# Auxillary.net
KiCad netlist of a schematic drawn in EAGLE
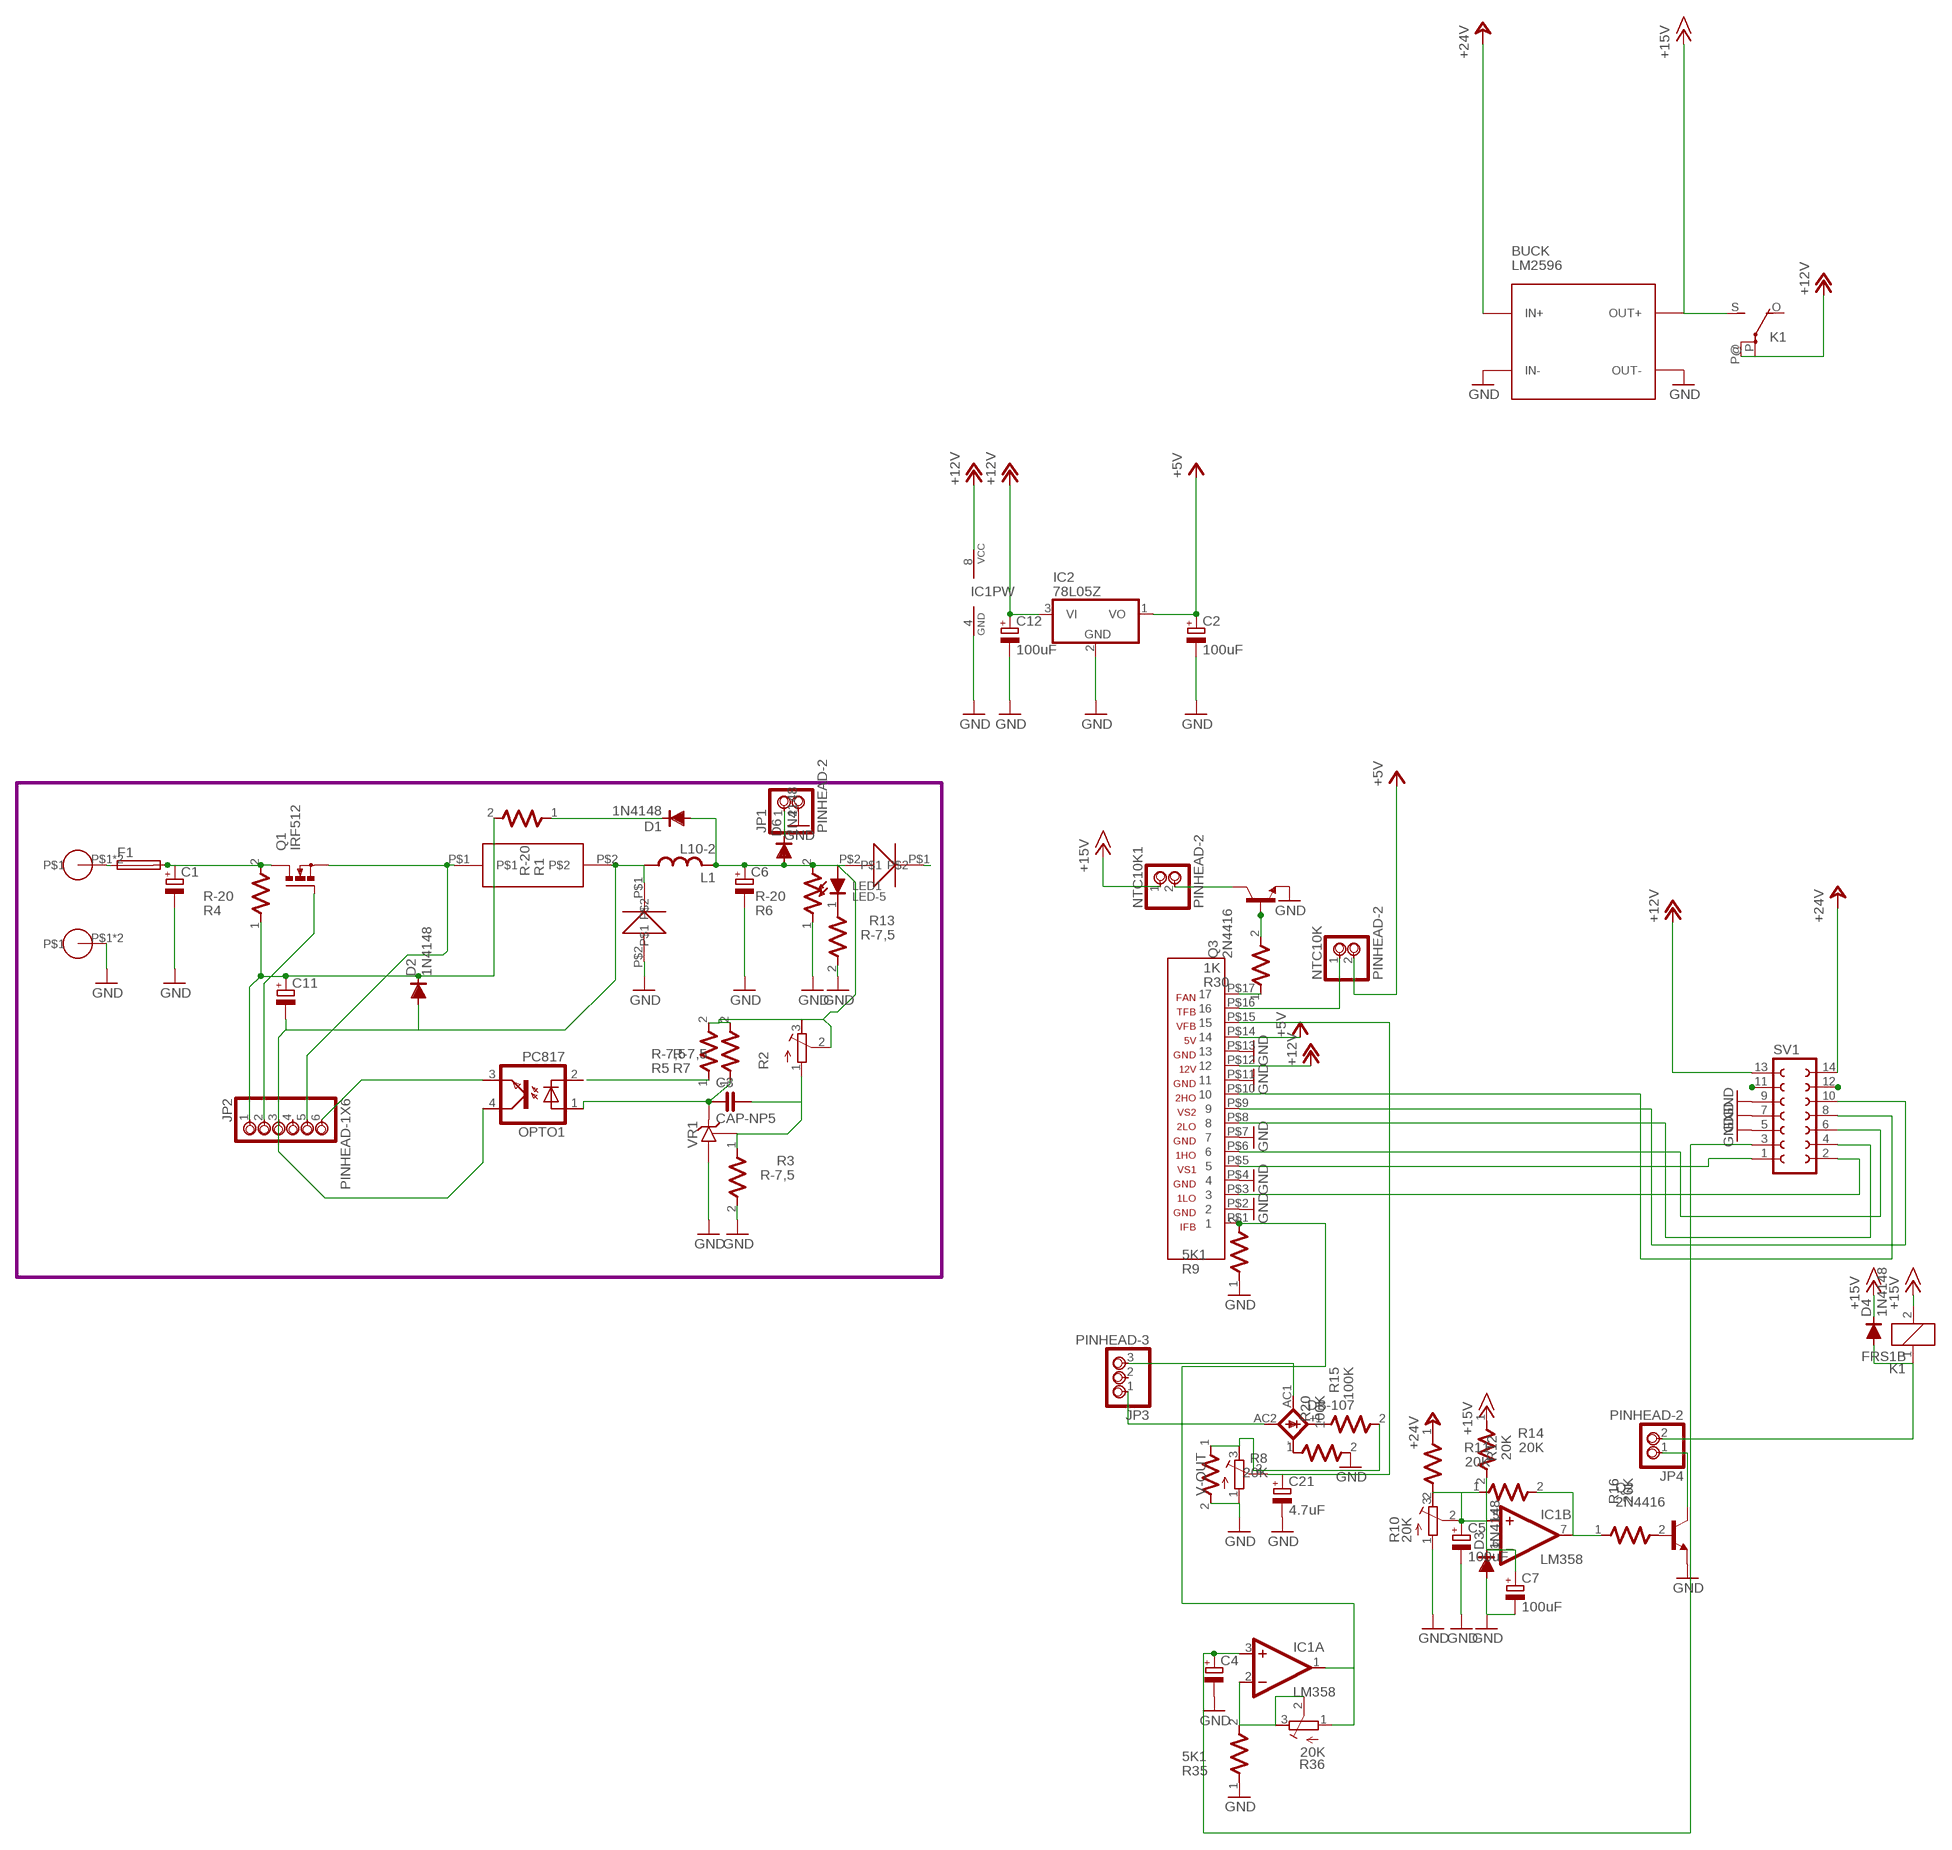
[diagram p0: schematic, sheet 1]

(export (version "E")
  (design (tool "Eeschema 10.0.6"))
  (components
    (comp (ref "BUCK")
      (value "LM2596")
      (footprint "eagle-import:DC-DC-STEP-DOWN-LM2596")
      (libsource (lib "eagle-import") (part "DC-DC-STEP-DOWN-LM2596"))
    )
    (comp (ref "C1")
      (value "CPOL-EUE7.5-18")
      (footprint "eagle-import:E7,5-18")
      (libsource (lib "eagle-import") (part "CPOL-EUE7.5-18"))
    )
    (comp (ref "C2")
      (value "100uF")
      (footprint "eagle-import:E2,5-7")
      (libsource (lib "eagle-import") (part "CPOL-EUE2.5-7"))
    )
    (comp (ref "C3")
      (value "CAP-NP5")
      (footprint "eagle-import:CAP-NP5")
      (libsource (lib "eagle-import") (part "CAP-NP5"))
    )
    (comp (ref "C4")
      (value "CPOL-EUE2.5-7")
      (footprint "eagle-import:E2,5-7")
      (libsource (lib "eagle-import") (part "CPOL-EUE2.5-7"))
    )
    (comp (ref "C5")
      (value "100uF")
      (footprint "eagle-import:E2,5-7")
      (libsource (lib "eagle-import") (part "CPOL-EUE2.5-7"))
    )
    (comp (ref "C6")
      (value "CPOL-EUE7.5-18")
      (footprint "eagle-import:E7,5-18")
      (libsource (lib "eagle-import") (part "CPOL-EUE7.5-18"))
    )
    (comp (ref "C7")
      (value "100uF")
      (footprint "eagle-import:E2,5-7")
      (libsource (lib "eagle-import") (part "CPOL-EUE2.5-7"))
    )
    (comp (ref "C11")
      (value "CPOL-EUE5-8.5")
      (footprint "eagle-import:E5-8,5")
      (libsource (lib "eagle-import") (part "CPOL-EUE5-8.5"))
    )
    (comp (ref "C12")
      (value "100uF")
      (footprint "eagle-import:E2,5-7")
      (libsource (lib "eagle-import") (part "CPOL-EUE2.5-7"))
    )
    (comp (ref "C21")
      (value "4.7uF")
      (footprint "eagle-import:E2,5-7")
      (libsource (lib "eagle-import") (part "CPOL-EUE2.5-7"))
    )
    (comp (ref "D1")
      (value "1N4148")
      (footprint "eagle-import:D-7,5")
      (libsource (lib "eagle-import") (part "1N4148"))
    )
    (comp (ref "D2")
      (value "1N4148")
      (footprint "eagle-import:D-7,5")
      (libsource (lib "eagle-import") (part "1N4148"))
    )
    (comp (ref "D3")
      (value "1N4148")
      (footprint "eagle-import:D-7,5")
      (libsource (lib "eagle-import") (part "1N4148"))
    )
    (comp (ref "D4")
      (value "1N4148")
      (footprint "eagle-import:D-7,5")
      (libsource (lib "eagle-import") (part "1N4148"))
    )
    (comp (ref "D6")
      (value "1N4148")
      (footprint "eagle-import:D-7,5")
      (libsource (lib "eagle-import") (part "1N4148"))
    )
    (comp (ref "DB-107")
      (value "CAU-1A")
      (footprint "eagle-import:CAU-1A")
      (libsource (lib "eagle-import") (part "CAU-1A"))
    )
    (comp (ref "F1")
      (value "SH22")
      (footprint "eagle-import:SH22")
      (libsource (lib "eagle-import") (part "SH22"))
    )
    (comp (ref "IC1")
      (value "LM358")
      (footprint "eagle-import:DIL-8")
      (libsource (lib "eagle-import") (part "LM358"))
    )
    (comp (ref "IC2")
      (value "78L05Z")
      (footprint "eagle-import:TO92")
      (libsource (lib "eagle-import") (part "78ZL05"))
    )
    (comp (ref "JP1")
      (value "PINHEAD-2")
      (footprint "eagle-import:PINHEAD-2")
      (libsource (lib "eagle-import") (part "chuong_PINHEAD-2"))
    )
    (comp (ref "JP2")
      (value "PINHEAD-1X6")
      (footprint "eagle-import:PINHEAD-1X6")
      (libsource (lib "eagle-import") (part "PINHEAD-1X6"))
    )
    (comp (ref "JP3")
      (value "PINHEAD-3")
      (footprint "eagle-import:PINHEAD-3")
      (libsource (lib "eagle-import") (part "PINHEAD-3"))
    )
    (comp (ref "JP4")
      (value "PINHEAD-2")
      (footprint "eagle-import:PINHEAD-2")
      (libsource (lib "eagle-import") (part "chuong_PINHEAD-2"))
    )
    (comp (ref "K1")
      (value "FRS1B")
      (footprint "eagle-import:FRS1B")
      (libsource (lib "eagle-import") (part "FRS1B"))
    )
    (comp (ref "L1")
      (value "L10-2")
      (footprint "eagle-import:L10-2")
      (libsource (lib "eagle-import") (part "L10-2"))
    )
    (comp (ref "LED1")
      (value "LED-5")
      (footprint "eagle-import:LED5")
      (libsource (lib "eagle-import") (part "LED-5"))
    )
    (comp (ref "NTC10K")
      (value "PINHEAD-2")
      (footprint "eagle-import:PINHEAD-2")
      (libsource (lib "eagle-import") (part "PINHEAD-2"))
    )
    (comp (ref "NTC10K1")
      (value "PINHEAD-2")
      (footprint "eagle-import:PINHEAD-2")
      (libsource (lib "eagle-import") (part "PINHEAD-2"))
    )
    (comp (ref "OPTO1")
      (value "PC817")
      (footprint "eagle-import:DIL-04")
      (libsource (lib "eagle-import") (part "PC817"))
    )
    (comp (ref "Q1")
      (value "IRF512")
      (footprint "eagle-import:TO220BV")
      (libsource (lib "eagle-import") (part "IRF512"))
    )
    (comp (ref "Q2")
      (value "2N4416")
      (footprint "eagle-import:TO92")
      (libsource (lib "eagle-import") (part "2N4416"))
    )
    (comp (ref "Q3")
      (value "2N4416")
      (footprint "eagle-import:TO92")
      (libsource (lib "eagle-import") (part "2N4416"))
    )
    (comp (ref "R1")
      (value "R-20")
      (footprint "eagle-import:R-20")
      (libsource (lib "eagle-import") (part "R-20"))
    )
    (comp (ref "R2")
      (value "R-TRIMM64W")
      (footprint "eagle-import:RTRIM64W")
      (libsource (lib "eagle-import") (part "R-TRIMM64W"))
    )
    (comp (ref "R3")
      (value "R-7,5")
      (footprint "eagle-import:R-7,5")
      (libsource (lib "eagle-import") (part "R-7,5"))
    )
    (comp (ref "R4")
      (value "R-20")
      (footprint "eagle-import:R-20")
      (libsource (lib "eagle-import") (part "R-20"))
    )
    (comp (ref "R5")
      (value "R-7,5")
      (footprint "eagle-import:R-7,5")
      (libsource (lib "eagle-import") (part "R-7,5"))
    )
    (comp (ref "R6")
      (value "R-20")
      (footprint "eagle-import:R-20")
      (libsource (lib "eagle-import") (part "R-20"))
    )
    (comp (ref "R7")
      (value "R-7,5")
      (footprint "eagle-import:R-7,5")
      (libsource (lib "eagle-import") (part "R-7,5"))
    )
    (comp (ref "R8")
      (value "20K")
      (footprint "eagle-import:R-7,5")
      (libsource (lib "eagle-import") (part "R-7,5"))
    )
    (comp (ref "R9")
      (value "5K1")
      (footprint "eagle-import:R-7,5")
      (libsource (lib "eagle-import") (part "R-7,5"))
    )
    (comp (ref "R10")
      (value "20K")
      (footprint "eagle-import:RTRIM64W")
      (libsource (lib "eagle-import") (part "R-TRIMM64W"))
    )
    (comp (ref "R11")
      (value "20K")
      (footprint "eagle-import:R-7,5")
      (libsource (lib "eagle-import") (part "R-7,5"))
    )
    (comp (ref "R12")
      (value "20K")
      (footprint "eagle-import:R-7,5")
      (libsource (lib "eagle-import") (part "R-7,5"))
    )
    (comp (ref "R13")
      (value "R-7,5")
      (footprint "eagle-import:R-7,5")
      (libsource (lib "eagle-import") (part "R-7,5"))
    )
    (comp (ref "R14")
      (value "20K")
      (footprint "eagle-import:R-7,5")
      (libsource (lib "eagle-import") (part "R-7,5"))
    )
    (comp (ref "R15")
      (value "100K")
      (footprint "eagle-import:R-7,5")
      (libsource (lib "eagle-import") (part "R-7,5"))
    )
    (comp (ref "R16")
      (value "20K")
      (footprint "eagle-import:R-7,5")
      (libsource (lib "eagle-import") (part "R-7,5"))
    )
    (comp (ref "R20")
      (value "100K")
      (footprint "eagle-import:R-7,5")
      (libsource (lib "eagle-import") (part "R-7,5"))
    )
    (comp (ref "R30")
      (value "1K")
      (footprint "eagle-import:R-7,5")
      (libsource (lib "eagle-import") (part "R-7,5"))
    )
    (comp (ref "R35")
      (value "5K1")
      (footprint "eagle-import:R-7,5")
      (libsource (lib "eagle-import") (part "R-7,5"))
    )
    (comp (ref "R36")
      (value "20K")
      (footprint "eagle-import:RTRIM64W")
      (libsource (lib "eagle-import") (part "R-TRIMM64W"))
    )
    (comp (ref "SV1")
      (value "FE07-2")
      (footprint "eagle-import:FE07-2")
      (libsource (lib "eagle-import") (part "FE07-2"))
    )
    (comp (ref "U$1")
      (value "DSEI6060A")
      (footprint "eagle-import:DSEI6060A")
      (libsource (lib "eagle-import") (part "DSEI6060A"))
    )
    (comp (ref "U$2")
      (value "DSEI6060A")
      (footprint "eagle-import:DSEI6060A")
      (libsource (lib "eagle-import") (part "DSEI6060A"))
    )
    (comp (ref "U$3")
      (value "PIN5MM")
      (footprint "eagle-import:PIN5MM")
      (libsource (lib "eagle-import") (part "PIN5MM"))
    )
    (comp (ref "U$4")
      (value "PIN5MM")
      (footprint "eagle-import:PIN5MM")
      (libsource (lib "eagle-import") (part "PIN5MM"))
    )
    (comp (ref "U$5")
      (value "SHUNT-0.01R")
      (footprint "eagle-import:SHUNT-0.01R")
      (libsource (lib "eagle-import") (part "SHUNT-0.01R"))
    )
    (comp (ref "U$11")
      (value "EGS002")
      (footprint "eagle-import:EGS002")
      (libsource (lib "eagle-import") (part "EGS002"))
    )
    (comp (ref "V-OUT")
      (value "R-TRIMM64W")
      (footprint "eagle-import:RTRIM64W")
      (libsource (lib "eagle-import") (part "R-TRIMM64W"))
    )
    (comp (ref "VR1")
      (value "TL431CLP")
      (footprint "eagle-import:TO92-CLP")
      (libsource (lib "eagle-import") (part "TL431CLP"))
    )
  )
  (nets
    (net (code "1") (name "+5V") (class "Default")
      (node (ref "C2") (pin "+") (pinfunction "+_+") (pintype "passive"))
      (node (ref "IC2") (pin "1") (pinfunction "VO_1") (pintype "passive"))
      (node (ref "NTC10K") (pin "2") (pinfunction "2_2") (pintype "passive"))
      (node (ref "U$11") (pin "P$14") (pinfunction "14_P$14") (pintype "bidirectional"))
    )
    (net (code "2") (name "+12V") (class "Default")
      (node (ref "C12") (pin "+") (pinfunction "+_+") (pintype "passive"))
      (node (ref "IC1") (pin "8") (pinfunction "VCC_8") (pintype "power_in"))
      (node (ref "IC2") (pin "3") (pinfunction "VI_3") (pintype "input"))
      (node (ref "K1") (pin "P") (pinfunction "P_P") (pintype "passive"))
      (node (ref "K1") (pin "P@") (pinfunction "P_P@") (pintype "passive"))
      (node (ref "SV1") (pin "13") (pinfunction "13_13") (pintype "passive"))
      (node (ref "U$11") (pin "P$12") (pinfunction "12_P$12") (pintype "bidirectional"))
    )
    (net (code "3") (name "+15V") (class "Default")
      (node (ref "BUCK") (pin "OUT+") (pinfunction "OUT+_OUT+") (pintype "bidirectional"))
      (node (ref "D4") (pin "C") (pinfunction "C_C") (pintype "passive"))
      (node (ref "K1") (pin "2") (pinfunction "2_2") (pintype "passive"))
      (node (ref "K1") (pin "S") (pinfunction "S_S") (pintype "passive"))
      (node (ref "NTC10K1") (pin "1") (pinfunction "1_1") (pintype "passive"))
      (node (ref "R14") (pin "1") (pinfunction "1_1") (pintype "passive"))
    )
    (net (code "4") (name "+24V") (class "Default")
      (node (ref "BUCK") (pin "IN+") (pinfunction "IN+_IN+") (pintype "bidirectional"))
      (node (ref "R11") (pin "1") (pinfunction "1_1") (pintype "passive"))
      (node (ref "SV1") (pin "14") (pinfunction "14_14") (pintype "passive"))
    )
    (net (code "5") (name "GND") (class "Default")
      (node (ref "BUCK") (pin "IN-") (pinfunction "IN-_IN-") (pintype "bidirectional"))
      (node (ref "BUCK") (pin "OUT-") (pinfunction "OUT-_OUT-") (pintype "bidirectional"))
      (node (ref "C1") (pin "-") (pinfunction "-_-") (pintype "passive"))
      (node (ref "C12") (pin "-") (pinfunction "-_-") (pintype "passive"))
      (node (ref "C2") (pin "-") (pinfunction "-_-") (pintype "passive"))
      (node (ref "C21") (pin "-") (pinfunction "-_-") (pintype "passive"))
      (node (ref "C4") (pin "-") (pinfunction "-_-") (pintype "passive"))
      (node (ref "C5") (pin "-") (pinfunction "-_-") (pintype "passive"))
      (node (ref "C6") (pin "-") (pinfunction "-_-") (pintype "passive"))
      (node (ref "C7") (pin "-") (pinfunction "-_-") (pintype "passive"))
      (node (ref "D3") (pin "A") (pinfunction "A_A") (pintype "passive"))
      (node (ref "IC1") (pin "4") (pinfunction "GND_4") (pintype "power_in"))
      (node (ref "IC2") (pin "2") (pinfunction "GND_2") (pintype "passive"))
      (node (ref "JP1") (pin "2") (pinfunction "2_2") (pintype "passive"))
      (node (ref "Q2") (pin "3") (pinfunction "E_3") (pintype "passive"))
      (node (ref "Q3") (pin "3") (pinfunction "E_3") (pintype "passive"))
      (node (ref "R10") (pin "1") (pinfunction "A_1") (pintype "passive"))
      (node (ref "R13") (pin "2") (pinfunction "2_2") (pintype "passive"))
      (node (ref "R20") (pin "2") (pinfunction "2_2") (pintype "passive"))
      (node (ref "R3") (pin "2") (pinfunction "2_2") (pintype "passive"))
      (node (ref "R35") (pin "1") (pinfunction "1_1") (pintype "passive"))
      (node (ref "R6") (pin "1") (pinfunction "1_1") (pintype "passive"))
      (node (ref "R8") (pin "2") (pinfunction "2_2") (pintype "passive"))
      (node (ref "R9") (pin "1") (pinfunction "1_1") (pintype "passive"))
      (node (ref "SV1") (pin "5") (pinfunction "5_5") (pintype "passive"))
      (node (ref "SV1") (pin "7") (pinfunction "7_7") (pintype "passive"))
      (node (ref "SV1") (pin "9") (pinfunction "9_9") (pintype "passive"))
      (node (ref "U$1") (pin "P$2") (pinfunction "P$2_P$2") (pintype "bidirectional"))
      (node (ref "U$11") (pin "P$11") (pinfunction "11_P$11") (pintype "bidirectional"))
      (node (ref "U$11") (pin "P$13") (pinfunction "13_P$13") (pintype "bidirectional"))
      (node (ref "U$11") (pin "P$2") (pinfunction "2_P$2") (pintype "bidirectional"))
      (node (ref "U$11") (pin "P$4") (pinfunction "4_P$4") (pintype "bidirectional"))
      (node (ref "U$11") (pin "P$7") (pinfunction "7_P$7") (pintype "bidirectional"))
      (node (ref "U$3") (pin "P$1") (pinfunction "P$1_P$1") (pintype "bidirectional"))
      (node (ref "U$3") (pin "P$2") (pinfunction "P$1_P$2") (pintype "bidirectional"))
      (node (ref "V-OUT") (pin "1") (pinfunction "A_1") (pintype "passive"))
      (node (ref "VR1") (pin "A") (pinfunction "A_A") (pintype "passive"))
    )
    (net (code "6") (name "Net-(D1-PadC)") (class "Default")
      (node (ref "D1") (pin "C") (pinfunction "C_C") (pintype "passive"))
      (node (ref "R1") (pin "1") (pinfunction "1_1") (pintype "passive"))
    )
    (net (code "7") (name "Net-(D4-PadA)") (class "Default")
      (node (ref "D4") (pin "A") (pinfunction "A_A") (pintype "passive"))
      (node (ref "JP4") (pin "2") (pinfunction "2_2") (pintype "passive"))
      (node (ref "K1") (pin "1") (pinfunction "1_1") (pintype "passive"))
    )
    (net (code "8") (name "Net-(D6-PadC)") (class "Default")
      (node (ref "D6") (pin "C") (pinfunction "C_C") (pintype "passive"))
      (node (ref "JP1") (pin "1") (pinfunction "1_1") (pintype "passive"))
    )
    (net (code "9") (name "Net-(DB-107--)") (class "Default")
      (node (ref "DB-107") (pin "AC2") (pinfunction "-_AC2") (pintype "passive"))
      (node (ref "JP3") (pin "1") (pinfunction "1_1") (pintype "passive"))
    )
    (net (code "10") (name "Net-(DB-107-AC2)") (class "Default")
      (node (ref "DB-107") (pin "-") (pinfunction "AC2_-") (pintype "passive"))
      (node (ref "R20") (pin "1") (pinfunction "1_1") (pintype "passive"))
    )
    (net (code "11") (name "Net-(DB-107-Pad+)") (class "Default")
      (node (ref "DB-107") (pin "+") (pinfunction "+_+") (pintype "passive"))
      (node (ref "R15") (pin "1") (pinfunction "1_1") (pintype "passive"))
    )
    (net (code "12") (name "Net-(DB-107-PadAC1)") (class "Default")
      (node (ref "DB-107") (pin "AC1") (pinfunction "AC1_AC1") (pintype "passive"))
      (node (ref "JP3") (pin "3") (pinfunction "3_3") (pintype "passive"))
    )
    (net (code "13") (name "Net-(F1-Pad1)") (class "Default")
      (node (ref "F1") (pin "1") (pinfunction "1_1") (pintype "passive"))
      (node (ref "U$4") (pin "P$1") (pinfunction "P$1_P$1") (pintype "bidirectional"))
      (node (ref "U$4") (pin "P$2") (pinfunction "P$1_P$2") (pintype "bidirectional"))
    )
    (net (code "14") (name "Net-(IC1A-+IN)") (class "Default")
      (node (ref "C4") (pin "+") (pinfunction "+_+") (pintype "passive"))
      (node (ref "IC1") (pin "3") (pinfunction "+IN_3") (pintype "input"))
      (node (ref "SV1") (pin "3") (pinfunction "3_3") (pintype "passive"))
    )
    (net (code "15") (name "Net-(IC1A--IN)") (class "Default")
      (node (ref "IC1") (pin "2") (pinfunction "-IN_2") (pintype "input"))
      (node (ref "R35") (pin "2") (pinfunction "2_2") (pintype "passive"))
      (node (ref "R36") (pin "2") (pinfunction "S_2") (pintype "passive"))
      (node (ref "R36") (pin "3") (pinfunction "E_3") (pintype "passive"))
    )
    (net (code "16") (name "Net-(IC1A-OUT)") (class "Default")
      (node (ref "IC1") (pin "1") (pinfunction "OUT_1") (pintype "output"))
      (node (ref "R36") (pin "1") (pinfunction "A_1") (pintype "passive"))
      (node (ref "R9") (pin "2") (pinfunction "2_2") (pintype "passive"))
      (node (ref "U$11") (pin "P$1") (pinfunction "1_P$1") (pintype "bidirectional"))
    )
    (net (code "17") (name "Net-(IC1B-+IN)") (class "Default")
      (node (ref "C5") (pin "+") (pinfunction "+_+") (pintype "passive"))
      (node (ref "IC1") (pin "5") (pinfunction "+IN_5") (pintype "input"))
      (node (ref "R10") (pin "2") (pinfunction "S_2") (pintype "passive"))
      (node (ref "R10") (pin "3") (pinfunction "E_3") (pintype "passive"))
      (node (ref "R11") (pin "2") (pinfunction "2_2") (pintype "passive"))
      (node (ref "R12") (pin "1") (pinfunction "1_1") (pintype "passive"))
    )
    (net (code "18") (name "Net-(IC1B--IN)") (class "Default")
      (node (ref "C7") (pin "+") (pinfunction "+_+") (pintype "passive"))
      (node (ref "D3") (pin "C") (pinfunction "C_C") (pintype "passive"))
      (node (ref "IC1") (pin "6") (pinfunction "-IN_6") (pintype "input"))
      (node (ref "R14") (pin "2") (pinfunction "2_2") (pintype "passive"))
    )
    (net (code "19") (name "Net-(IC1B-OUT)") (class "Default")
      (node (ref "IC1") (pin "7") (pinfunction "OUT_7") (pintype "output"))
      (node (ref "R12") (pin "2") (pinfunction "2_2") (pintype "passive"))
      (node (ref "R16") (pin "1") (pinfunction "1_1") (pintype "passive"))
    )
    (net (code "20") (name "Net-(JP2-Pad2)") (class "Default")
      (node (ref "JP2") (pin "2") (pinfunction "2_2") (pintype "passive"))
      (node (ref "Q1") (pin "G") (pinfunction "G_G") (pintype "passive"))
    )
    (net (code "21") (name "Net-(JP2-Pad5)") (class "Default")
      (node (ref "JP2") (pin "5") (pinfunction "5_5") (pintype "passive"))
      (node (ref "Q1") (pin "S") (pinfunction "S_S") (pintype "passive"))
      (node (ref "U$5") (pin "P$1") (pinfunction "P$1_P$1") (pintype "bidirectional"))
    )
    (net (code "22") (name "Net-(LED1-PadK)") (class "Default")
      (node (ref "LED1") (pin "K") (pinfunction "K_K") (pintype "passive"))
      (node (ref "R13") (pin "1") (pinfunction "1_1") (pintype "passive"))
    )
    (net (code "23") (name "Net-(OPTO1-A)") (class "Default")
      (node (ref "C3") (pin "1") (pinfunction "1_1") (pintype "passive"))
      (node (ref "OPTO1") (pin "1") (pinfunction "A_1") (pintype "passive"))
      (node (ref "R7") (pin "1") (pinfunction "1_1") (pintype "passive"))
      (node (ref "VR1") (pin "C") (pinfunction "C_C") (pintype "passive"))
    )
    (net (code "24") (name "Net-(OPTO1-COL)") (class "Default")
      (node (ref "C11") (pin "-") (pinfunction "-_-") (pintype "passive"))
      (node (ref "D2") (pin "A") (pinfunction "A_A") (pintype "passive"))
      (node (ref "JP2") (pin "3") (pinfunction "3_3") (pintype "passive"))
      (node (ref "L1") (pin "P$1") (pinfunction "1_P$1") (pintype "passive"))
      (node (ref "L1") (pin "P$2") (pinfunction "1_P$2") (pintype "passive"))
      (node (ref "OPTO1") (pin "4") (pinfunction "COL_4") (pintype "passive"))
      (node (ref "U$1") (pin "P$1") (pinfunction "P$1_P$1") (pintype "bidirectional"))
      (node (ref "U$5") (pin "P$2") (pinfunction "P$2_P$2") (pintype "bidirectional"))
    )
    (net (code "25") (name "Net-(OPTO1-EMI)") (class "Default")
      (node (ref "JP2") (pin "6") (pinfunction "6_6") (pintype "passive"))
      (node (ref "OPTO1") (pin "3") (pinfunction "EMI_3") (pintype "passive"))
    )
    (net (code "26") (name "Net-(Q2-B)") (class "Default")
      (node (ref "Q2") (pin "2") (pinfunction "B_2") (pintype "passive"))
      (node (ref "R16") (pin "2") (pinfunction "2_2") (pintype "passive"))
    )
    (net (code "27") (name "Net-(Q2-C)") (class "Default")
      (node (ref "JP4") (pin "1") (pinfunction "1_1") (pintype "passive"))
      (node (ref "Q2") (pin "1") (pinfunction "C_1") (pintype "passive"))
    )
    (net (code "28") (name "Net-(Q3-B)") (class "Default")
      (node (ref "Q3") (pin "2") (pinfunction "B_2") (pintype "passive"))
      (node (ref "R30") (pin "2") (pinfunction "2_2") (pintype "passive"))
    )
    (net (code "29") (name "Net-(Q3-C)") (class "Default")
      (node (ref "NTC10K1") (pin "2") (pinfunction "2_2") (pintype "passive"))
      (node (ref "Q3") (pin "1") (pinfunction "C_1") (pintype "passive"))
    )
    (net (code "30") (name "Net-(R1-3)") (class "Default")
      (node (ref "C11") (pin "+") (pinfunction "+_+") (pintype "passive"))
      (node (ref "D2") (pin "C") (pinfunction "C_C") (pintype "passive"))
      (node (ref "JP2") (pin "1") (pinfunction "1_1") (pintype "passive"))
      (node (ref "R1") (pin "2") (pinfunction "3_2") (pintype "passive"))
      (node (ref "R4") (pin "1") (pinfunction "1_1") (pintype "passive"))
    )
    (net (code "31") (name "Net-(R2-A)") (class "Default")
      (node (ref "C3") (pin "2") (pinfunction "2_2") (pintype "passive"))
      (node (ref "R2") (pin "1") (pinfunction "A_1") (pintype "passive"))
      (node (ref "R3") (pin "1") (pinfunction "1_1") (pintype "passive"))
      (node (ref "VR1") (pin "R") (pinfunction "R_R") (pintype "passive"))
    )
    (net (code "32") (name "Net-(R2-E)") (class "Default")
      (node (ref "C6") (pin "+") (pinfunction "+_+") (pintype "passive"))
      (node (ref "D1") (pin "A") (pinfunction "A_A") (pintype "passive"))
      (node (ref "D6") (pin "A") (pinfunction "A_A") (pintype "passive"))
      (node (ref "L1") (pin "P$3") (pinfunction "2_P$3") (pintype "passive"))
      (node (ref "L1") (pin "P$4") (pinfunction "2_P$4") (pintype "passive"))
      (node (ref "LED1") (pin "A") (pinfunction "A_A") (pintype "passive"))
      (node (ref "R2") (pin "2") (pinfunction "S_2") (pintype "passive"))
      (node (ref "R2") (pin "3") (pinfunction "E_3") (pintype "passive"))
      (node (ref "R5") (pin "2") (pinfunction "2_2") (pintype "passive"))
      (node (ref "R6") (pin "2") (pinfunction "3_2") (pintype "passive"))
      (node (ref "R7") (pin "2") (pinfunction "2_2") (pintype "passive"))
      (node (ref "U$2") (pin "P$2") (pinfunction "P$2_P$2") (pintype "bidirectional"))
    )
    (net (code "33") (name "Net-(R4-3)") (class "Default")
      (node (ref "C1") (pin "+") (pinfunction "+_+") (pintype "passive"))
      (node (ref "F1") (pin "2") (pinfunction "2_2") (pintype "passive"))
      (node (ref "Q1") (pin "D") (pinfunction "D_D") (pintype "passive"))
      (node (ref "R4") (pin "2") (pinfunction "3_2") (pintype "passive"))
    )
    (net (code "34") (name "Net-(U$11-3)") (class "Default")
      (node (ref "SV1") (pin "2") (pinfunction "2_2") (pintype "passive"))
      (node (ref "U$11") (pin "P$3") (pinfunction "3_P$3") (pintype "bidirectional"))
    )
    (net (code "35") (name "Net-(U$11-5)") (class "Default")
      (node (ref "SV1") (pin "1") (pinfunction "1_1") (pintype "passive"))
      (node (ref "U$11") (pin "P$5") (pinfunction "5_P$5") (pintype "bidirectional"))
    )
    (net (code "36") (name "Net-(U$11-6)") (class "Default")
      (node (ref "SV1") (pin "6") (pinfunction "6_6") (pintype "passive"))
      (node (ref "U$11") (pin "P$6") (pinfunction "6_P$6") (pintype "bidirectional"))
    )
    (net (code "37") (name "Net-(U$11-8)") (class "Default")
      (node (ref "SV1") (pin "4") (pinfunction "4_4") (pintype "passive"))
      (node (ref "U$11") (pin "P$8") (pinfunction "8_P$8") (pintype "bidirectional"))
    )
    (net (code "38") (name "Net-(U$11-9)") (class "Default")
      (node (ref "SV1") (pin "10") (pinfunction "10_10") (pintype "passive"))
      (node (ref "U$11") (pin "P$9") (pinfunction "9_P$9") (pintype "bidirectional"))
    )
    (net (code "39") (name "Net-(U$11-10)") (class "Default")
      (node (ref "SV1") (pin "8") (pinfunction "8_8") (pintype "passive"))
      (node (ref "U$11") (pin "P$10") (pinfunction "10_P$10") (pintype "bidirectional"))
    )
    (net (code "40") (name "Net-(U$11-15)") (class "Default")
      (node (ref "C21") (pin "+") (pinfunction "+_+") (pintype "passive"))
      (node (ref "U$11") (pin "P$15") (pinfunction "15_P$15") (pintype "bidirectional"))
      (node (ref "V-OUT") (pin "2") (pinfunction "S_2") (pintype "passive"))
    )
    (net (code "41") (name "Net-(U$11-16)") (class "Default")
      (node (ref "NTC10K") (pin "1") (pinfunction "1_1") (pintype "passive"))
      (node (ref "U$11") (pin "P$16") (pinfunction "16_P$16") (pintype "bidirectional"))
    )
    (net (code "42") (name "Net-(U$11-17)") (class "Default")
      (node (ref "R30") (pin "1") (pinfunction "1_1") (pintype "passive"))
      (node (ref "U$11") (pin "P$17") (pinfunction "17_P$17") (pintype "bidirectional"))
    )
    (net (code "43") (name "Net-(V-OUT-E)") (class "Default")
      (node (ref "R15") (pin "2") (pinfunction "2_2") (pintype "passive"))
      (node (ref "R8") (pin "1") (pinfunction "1_1") (pintype "passive"))
      (node (ref "V-OUT") (pin "3") (pinfunction "E_3") (pintype "passive"))
    )
    (net (code "44") (name "unconnected-(JP2-Pad4)") (class "Default")
      (node (ref "JP2") (pin "4") (pinfunction "4_4") (pintype "passive"))
    )
    (net (code "45") (name "unconnected-(JP3-Pad2)") (class "Default")
      (node (ref "JP3") (pin "2") (pinfunction "2_2") (pintype "passive"))
    )
    (net (code "46") (name "unconnected-(K1-PadO)") (class "Default")
      (node (ref "K1") (pin "O") (pinfunction "O_O") (pintype "passive"))
    )
    (net (code "47") (name "unconnected-(OPTO1-C-Pad2)") (class "Default")
      (node (ref "OPTO1") (pin "2") (pinfunction "C_2") (pintype "passive"))
    )
    (net (code "48") (name "unconnected-(R5-Pad1)") (class "Default")
      (node (ref "R5") (pin "1") (pinfunction "1_1") (pintype "passive"))
    )
    (net (code "49") (name "unconnected-(SV1-Pad11)") (class "Default")
      (node (ref "SV1") (pin "11") (pinfunction "11_11") (pintype "passive"))
    )
    (net (code "50") (name "unconnected-(SV1-Pad12)") (class "Default")
      (node (ref "SV1") (pin "12") (pinfunction "12_12") (pintype "passive"))
    )
    (net (code "51") (name "unconnected-(U$2-PadP$1)") (class "Default")
      (node (ref "U$2") (pin "P$1") (pinfunction "P$1_P$1") (pintype "bidirectional"))
    )
  )
)
